# Barrido_DC.net
KiCad netlist of a schematic drawn in Altium Designer
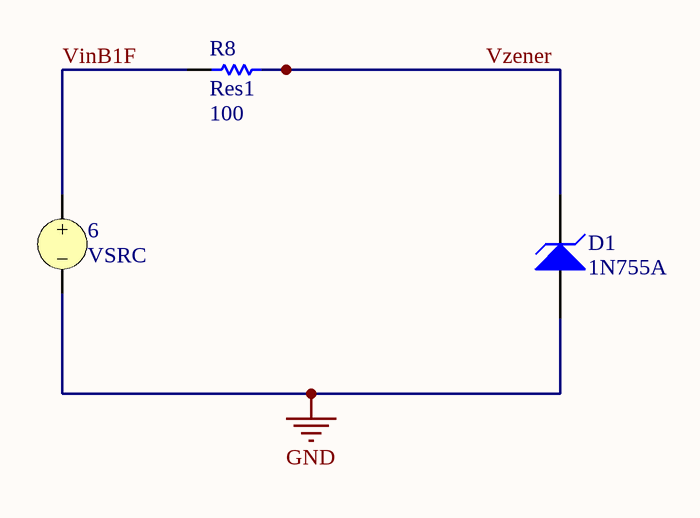
[diagram p0: Barrido DC.SchDoc]

(export (version "E")
  (design (tool "Eeschema 10.0.6"))
  (components
    (comp (ref "6")
      (value "VSRC")
      (description "Voltage Source")
      (fields (field (name "PUBLISHER") "Altium Limited"))
      (libsource (lib "Simulation Sources") (part "VSRC"))
    )
    (comp (ref "D1")
      (value "1N755A")
      (footprint "DO-35")
      (description "Half Watt Zener")
      (fields (field (name "PUBLISHER") "Altium Limited"))
      (libsource (lib "altium-import") (part "root_1_1N755A_"))
    )
    (comp (ref "R8")
      (value "Res1")
      (footprint "AXIAL-0.3")
      (description "Resistor")
      (fields (field (name "ALTIUM_VALUE") "100") (field (name "PUBLISHER") "Altium Limited"))
      (libsource (lib "Miscellaneous Devices") (part "Res1"))
    )
  )
  (nets
    (net (code "1") (name "/VinB1F") (class "Default")
      (node (ref "6") (pin "1") (pinfunction "1_1") (pintype "passive"))
      (node (ref "R8") (pin "1") (pinfunction "1_1") (pintype "passive"))
    )
    (net (code "2") (name "/Vzener") (class "Default")
      (node (ref "D1") (pin "2") (pinfunction "K_2") (pintype "passive"))
      (node (ref "R8") (pin "2") (pinfunction "2_2") (pintype "passive"))
    )
    (net (code "3") (name "GND") (class "Default")
      (node (ref "6") (pin "2") (pinfunction "2_2") (pintype "passive"))
      (node (ref "D1") (pin "1") (pinfunction "A_1") (pintype "passive"))
    )
  )
)
